# InputChannel_2.net
KiCad netlist of a schematic drawn in Altium Designer
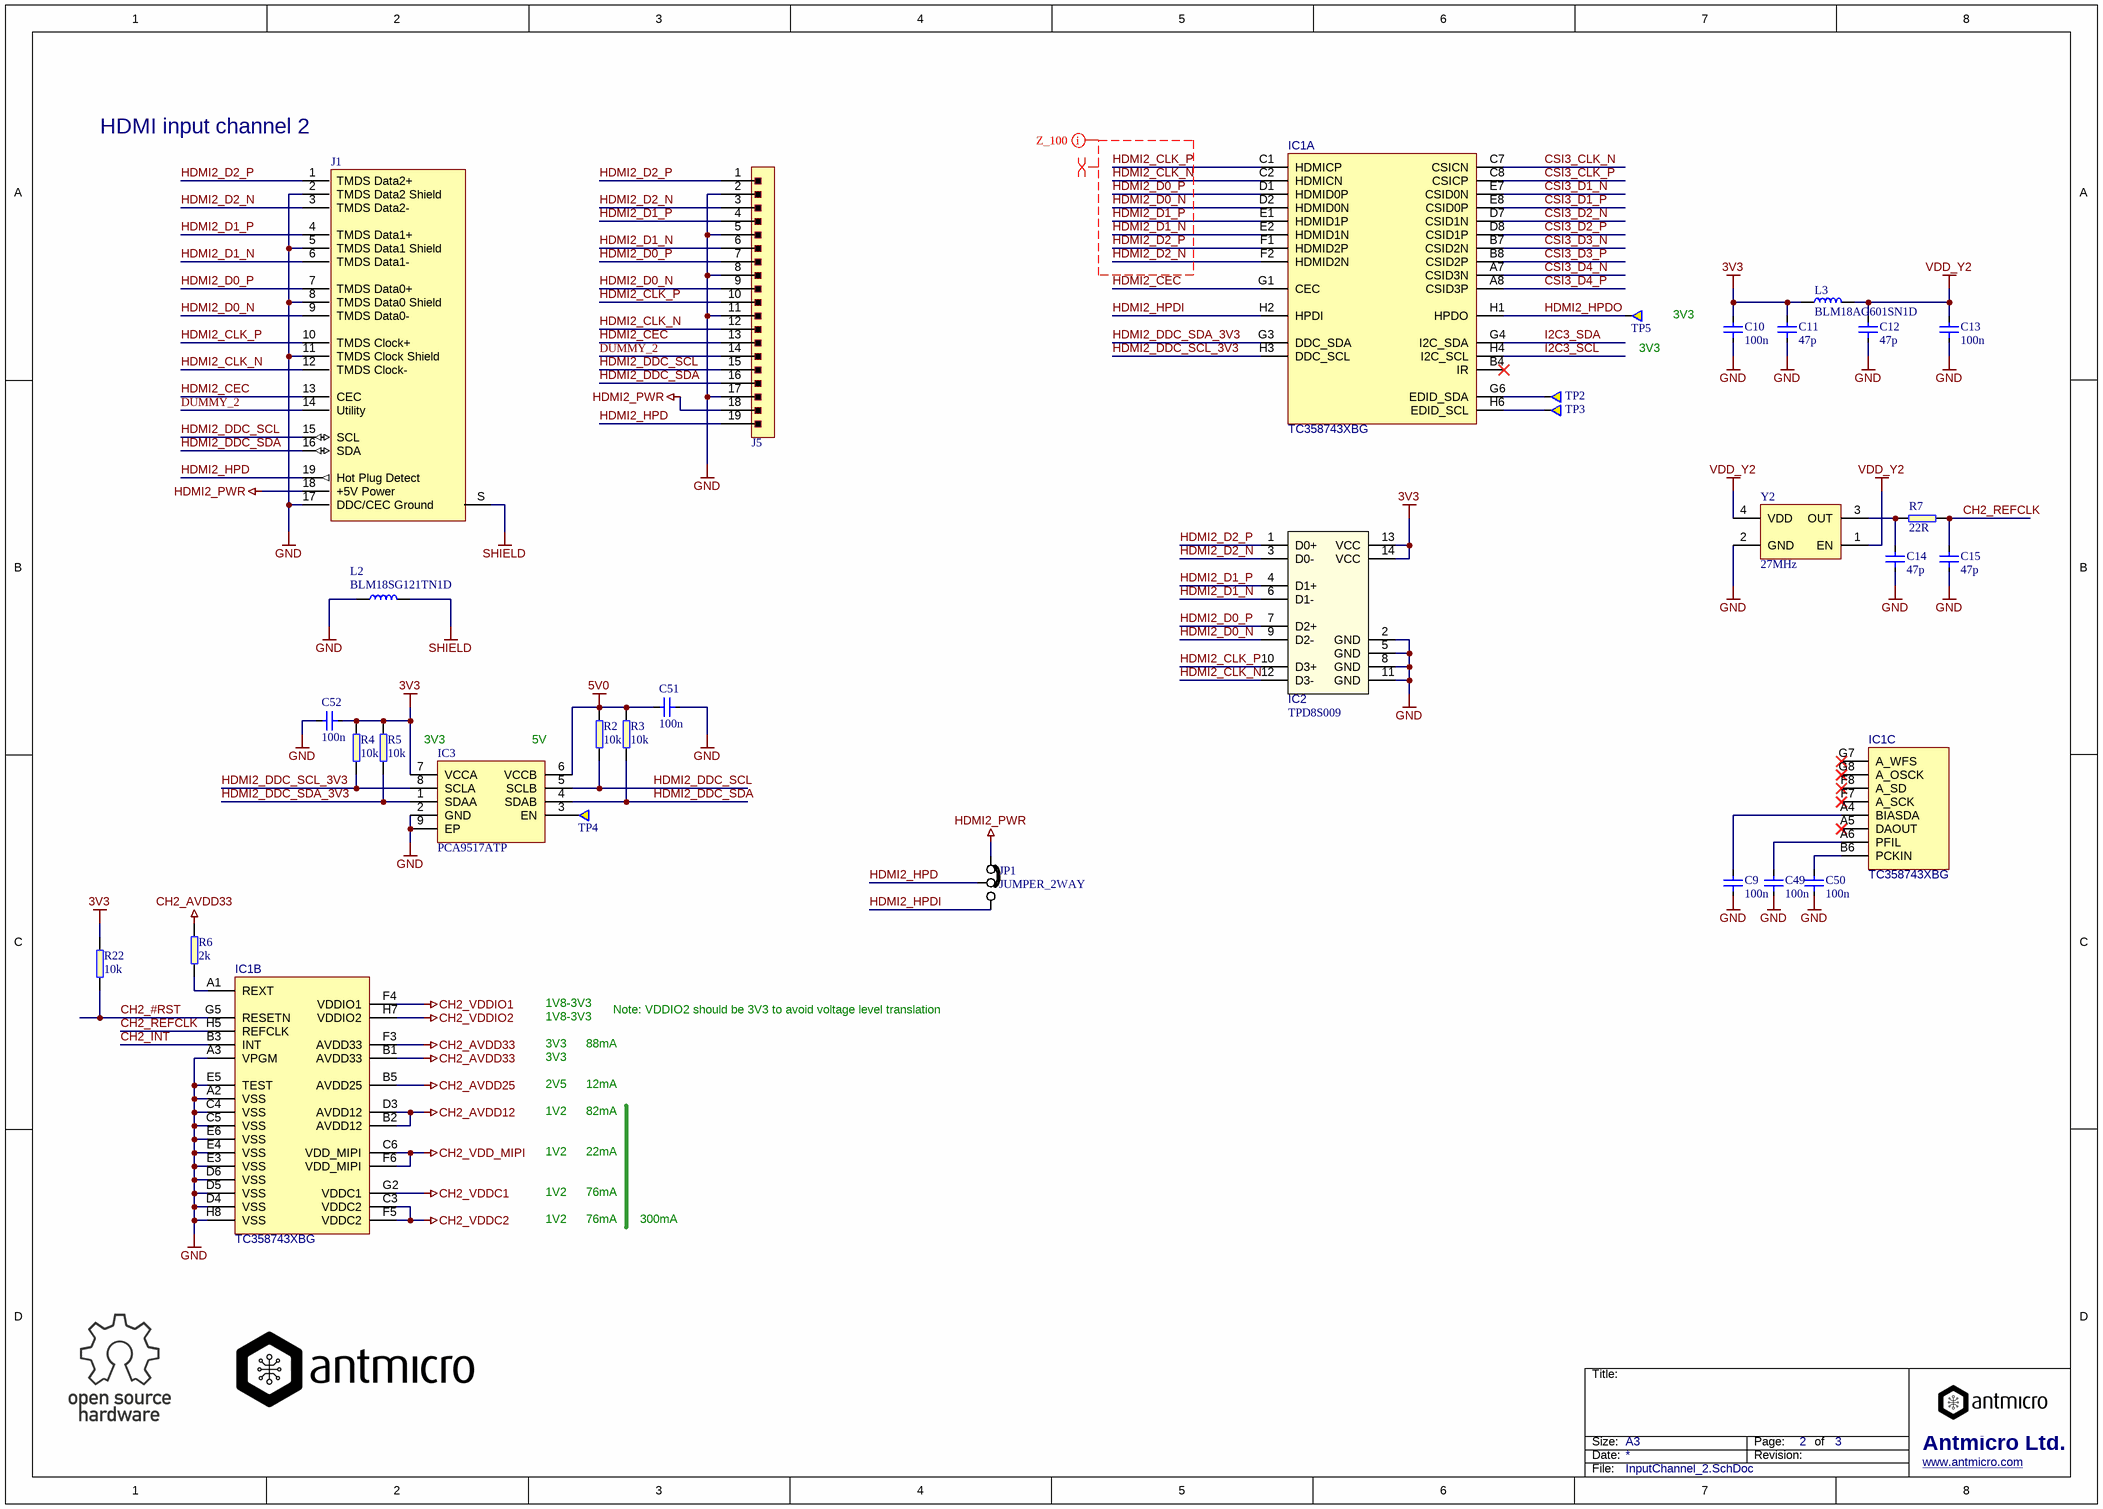
[diagram p0: InputChannel_2.SchDoc]

(export (version "E")
  (design (tool "Eeschema 10.0.6"))
  (components
    (comp (ref "C9")
      (value "100n")
      (footprint "HDMI-MIPI-Bridge:0402")
      (description "MLCC SMT Capacitor 100nF 0402")
      (fields (field (name "PART NUMBER") "C_100n_0402") (field (name "MANUFACTURER") "MULTICOMP"))
      (libsource (lib "AntmicroComponents") (part "C"))
    )
    (comp (ref "C10")
      (value "100n")
      (footprint "HDMI-MIPI-Bridge:0402")
      (description "MLCC SMT Capacitor 100nF 0402")
      (fields (field (name "PART NUMBER") "C_100n_0402") (field (name "MANUFACTURER") "MULTICOMP"))
      (libsource (lib "AntmicroComponents") (part "C"))
    )
    (comp (ref "C11")
      (value "47p")
      (footprint "HDMI-MIPI-Bridge:0402")
      (description "MLCC SMT Capacitor 47pF 0402")
      (fields (field (name "PART NUMBER") "C_47p_0402") (field (name "MANUFACTURER") "KEMET"))
      (libsource (lib "AntmicroComponents") (part "C"))
    )
    (comp (ref "C12")
      (value "47p")
      (footprint "HDMI-MIPI-Bridge:0402")
      (description "MLCC SMT Capacitor 47pF 0402")
      (fields (field (name "PART NUMBER") "C_47p_0402") (field (name "MANUFACTURER") "KEMET"))
      (libsource (lib "AntmicroComponents") (part "C"))
    )
    (comp (ref "C13")
      (value "100n")
      (footprint "HDMI-MIPI-Bridge:0402")
      (description "MLCC SMT Capacitor 100nF 0402")
      (fields (field (name "PART NUMBER") "C_100n_0402") (field (name "MANUFACTURER") "MULTICOMP"))
      (libsource (lib "AntmicroComponents") (part "C"))
    )
    (comp (ref "C14")
      (value "47p")
      (footprint "HDMI-MIPI-Bridge:0402")
      (description "MLCC SMT Capacitor 47pF 0402")
      (fields (field (name "PART NUMBER") "C_47p_0402") (field (name "MANUFACTURER") "KEMET"))
      (libsource (lib "AntmicroComponents") (part "C"))
    )
    (comp (ref "C15")
      (value "47p")
      (footprint "HDMI-MIPI-Bridge:0402")
      (description "MLCC SMT Capacitor 47pF 0402")
      (fields (field (name "PART NUMBER") "C_47p_0402") (field (name "MANUFACTURER") "KEMET"))
      (libsource (lib "AntmicroComponents") (part "C"))
    )
    (comp (ref "C49")
      (value "100n")
      (footprint "HDMI-MIPI-Bridge:0402")
      (description "MLCC SMT Capacitor 100nF 0402")
      (fields (field (name "PART NUMBER") "C_100n_0402") (field (name "MANUFACTURER") "MULTICOMP"))
      (libsource (lib "AntmicroComponents") (part "C"))
    )
    (comp (ref "C50")
      (value "100n")
      (footprint "HDMI-MIPI-Bridge:0402")
      (description "MLCC SMT Capacitor 100nF 0402")
      (fields (field (name "PART NUMBER") "C_100n_0402") (field (name "MANUFACTURER") "MULTICOMP"))
      (libsource (lib "AntmicroComponents") (part "C"))
    )
    (comp (ref "C51")
      (value "100n")
      (footprint "HDMI-MIPI-Bridge:0402")
      (description "MLCC SMT Capacitor 100nF 0402")
      (fields (field (name "PART NUMBER") "C_100n_0402") (field (name "MANUFACTURER") "MULTICOMP"))
      (libsource (lib "AntmicroComponents") (part "C"))
    )
    (comp (ref "C52")
      (value "100n")
      (footprint "HDMI-MIPI-Bridge:0402")
      (description "MLCC SMT Capacitor 100nF 0402")
      (fields (field (name "PART NUMBER") "C_100n_0402") (field (name "MANUFACTURER") "MULTICOMP"))
      (libsource (lib "AntmicroComponents") (part "C"))
    )
    (comp (ref "IC1")
      (value "TC358743XBG")
      (footprint "HDMI-MIPI-Bridge:TC358743XBG")
      (description "Toshiba TC358743XBG HDMI-CSI bridge")
      (fields (field (name "MANUFACTURER") "Toshiba"))
      (libsource (lib "AntmicroComponents") (part "TC358743XBG"))
    )
    (comp (ref "IC2")
      (value "TPD8S009")
      (footprint "HDMI-MIPI-Bridge:SON-15")
      (description "8-Channel ESD Protection for DisplayPort and HDMI")
      (fields (field (name "MANUFACTURER") "TEXAS INSTRUMENTS") (field (name "MPN") "TPD8S009DSMR"))
      (libsource (lib "AntmicroComponents") (part "TPD8S009"))
    )
    (comp (ref "IC3")
      (value "PCA9517ATP")
      (footprint "HDMI-MIPI-Bridge:PCA9517ATP")
      (description "I2C BUS REPEATER W/ LEVEL TRANS, HWSON-8")
      (fields (field (name "MANUFACTURER") "NXP"))
      (libsource (lib "AntmicroComponents") (part "PCA9517ATP"))
    )
    (comp (ref "J1")
      (value "~")
      (footprint "HDMI-MIPI-Bridge:Molex_HDMI_471511001")
      (description "Header right angle HDMI")
      (fields (field (name "PART NUMBER") "CON-Molex-471511001") (field (name "MANUFACTURER") "MOLEX"))
      (libsource (lib "AntmicroComponents") (part "CON-Molex-471511001"))
    )
    (comp (ref "J5")
      (value "Molex-505110-1992")
      (footprint "HDMI-MIPI-Bridge:CON-Molex-505110-1992")
      (description "FPC socket 19 pins")
      (fields (field (name "PART NUMBER") "CON-Molex-505110-1992") (field (name "MANUFACTURER") "Molex"))
      (libsource (lib "AntmicroComponents") (part "1X19"))
    )
    (comp (ref "JP1")
      (value "JUMPER_2WAY")
      (footprint "HDMI-MIPI-Bridge:JUMPER_2WAY")
      (description "Solder jumper")
      (fields (field (name "PART NUMBER") "Jumper 2 way"))
      (libsource (lib "AntmicroComponents") (part "JUMPER_2WAY"))
    )
    (comp (ref "L2")
      (value "BLM18SG121TN1D")
      (footprint "HDMI-MIPI-Bridge:0603")
      (description "FERRITE BEAD, 0.025OHM, 3A, 0603")
      (fields (field (name "MANUFACTURER") "MURATA"))
      (libsource (lib "AntmicroComponents") (part "Inductor SMT"))
    )
    (comp (ref "L3")
      (value "BLM18AG601SN1D")
      (footprint "HDMI-MIPI-Bridge:0603")
      (description "Ferrite Bead, 600 ohm, 0603 [1608 Metric], BLM18A Series, 500 mA, 0.38 ohm, ± 25%")
      (fields (field (name "MANUFACTURER") "MURATA"))
      (libsource (lib "AntmicroComponents") (part "Inductor SMT"))
    )
    (comp (ref "R2")
      (value "10k")
      (footprint "HDMI-MIPI-Bridge:0402")
      (description "SMT Resistor 0402")
      (fields (field (name "PART NUMBER") "R_10k_0402") (field (name "MANUFACTURER") "MULTICOMP"))
      (libsource (lib "AntmicroComponents") (part "R"))
    )
    (comp (ref "R3")
      (value "10k")
      (footprint "HDMI-MIPI-Bridge:0402")
      (description "SMT Resistor 0402")
      (fields (field (name "PART NUMBER") "R_10k_0402") (field (name "MANUFACTURER") "MULTICOMP"))
      (libsource (lib "AntmicroComponents") (part "R"))
    )
    (comp (ref "R4")
      (value "10k")
      (footprint "HDMI-MIPI-Bridge:0402")
      (description "SMT Resistor 0402")
      (fields (field (name "PART NUMBER") "R_10k_0402") (field (name "MANUFACTURER") "MULTICOMP"))
      (libsource (lib "AntmicroComponents") (part "R"))
    )
    (comp (ref "R5")
      (value "10k")
      (footprint "HDMI-MIPI-Bridge:0402")
      (description "SMT Resistor 0402")
      (fields (field (name "PART NUMBER") "R_10k_0402") (field (name "MANUFACTURER") "MULTICOMP"))
      (libsource (lib "AntmicroComponents") (part "R"))
    )
    (comp (ref "R6")
      (value "2k")
      (footprint "HDMI-MIPI-Bridge:0603")
      (description "SMT Resistor 2k 0603")
      (fields (field (name "PART NUMBER") "R_2k_0603") (field (name "MANUFACTURER") "MULTICOMP"))
      (libsource (lib "AntmicroComponents") (part "R"))
    )
    (comp (ref "R7")
      (value "22R")
      (footprint "HDMI-MIPI-Bridge:0402")
      (description "SMT Resistor 22R 0402")
      (fields (field (name "PART NUMBER") "R_22R_0402") (field (name "MANUFACTURER") "VISHAY"))
      (libsource (lib "") (part "R_1"))
    )
    (comp (ref "R22")
      (value "10k")
      (footprint "HDMI-MIPI-Bridge:0402")
      (description "SMT Resistor 0402")
      (fields (field (name "PART NUMBER") "R_10k_0402") (field (name "MANUFACTURER") "MULTICOMP"))
      (libsource (lib "AntmicroComponents") (part "R"))
    )
    (comp (ref "TP2")
      (value "Testpad")
      (footprint "HDMI-MIPI-Bridge:TP-R-1")
      (description "Testpad, round, 1mm")
      (fields (field (name "PART NUMBER") "TP-R-1"))
      (libsource (lib "AntmicroComponents") (part "Testpad"))
    )
    (comp (ref "TP3")
      (value "Testpad")
      (footprint "HDMI-MIPI-Bridge:TP-R-1")
      (description "Testpad, round, 1mm")
      (fields (field (name "PART NUMBER") "TP-R-1"))
      (libsource (lib "AntmicroComponents") (part "Testpad"))
    )
    (comp (ref "TP4")
      (value "Testpad")
      (footprint "HDMI-MIPI-Bridge:TP-R-1")
      (description "Testpad, round, 1mm")
      (fields (field (name "PART NUMBER") "TP-R-1"))
      (libsource (lib "AntmicroComponents") (part "Testpad"))
    )
    (comp (ref "TP5")
      (value "Testpad")
      (footprint "HDMI-MIPI-Bridge:TP-R-1")
      (description "Testpad, round, 1mm")
      (fields (field (name "PART NUMBER") "TP-R-1"))
      (libsource (lib "AntmicroComponents") (part "Testpad"))
    )
    (comp (ref "Y2")
      (value "27MHz")
      (footprint "HDMI-MIPI-Bridge:TXC_7C")
      (description "OSC, 27.000MHZ, 3.3V, SMD, 5.0X3.2")
      (fields (field (name "PART NUMBER") "7C-27.000MBB-T") (field (name "MANUFACTURER") "TXC"))
      (libsource (lib "AntmicroComponents") (part "TXC_7C"))
    )
  )
  (nets
    (net (code "1") (name "/CH2_#RST") (class "Default")
      (node (ref "IC1") (pin "G5") (pinfunction "RESETN_G5") (pintype "passive"))
      (node (ref "R22") (pin "1") (pintype "passive"))
    )
    (net (code "2") (name "/CH2_INT") (class "Default")
      (node (ref "IC1") (pin "B3") (pinfunction "INT_B3") (pintype "passive"))
    )
    (net (code "3") (name "/CH2_REFCLK") (class "Default")
      (node (ref "C15") (pin "2") (pinfunction "2_2") (pintype "passive"))
      (node (ref "IC1") (pin "H5") (pinfunction "REFCLK_H5") (pintype "passive"))
      (node (ref "R7") (pin "2") (pintype "passive"))
    )
    (net (code "4") (name "/CSI3_CLK_N") (class "Default")
      (node (ref "IC1") (pin "C7") (pinfunction "CSICN_C7") (pintype "passive"))
    )
    (net (code "5") (name "/CSI3_CLK_P") (class "Default")
      (node (ref "IC1") (pin "C8") (pinfunction "CSICP_C8") (pintype "passive"))
    )
    (net (code "6") (name "/CSI3_D1_N") (class "Default")
      (node (ref "IC1") (pin "E7") (pinfunction "CSID0N_E7") (pintype "passive"))
    )
    (net (code "7") (name "/CSI3_D1_P") (class "Default")
      (node (ref "IC1") (pin "E8") (pinfunction "CSID0P_E8") (pintype "passive"))
    )
    (net (code "8") (name "/CSI3_D2_N") (class "Default")
      (node (ref "IC1") (pin "D7") (pinfunction "CSID1N_D7") (pintype "passive"))
    )
    (net (code "9") (name "/CSI3_D2_P") (class "Default")
      (node (ref "IC1") (pin "D8") (pinfunction "CSID1P_D8") (pintype "passive"))
    )
    (net (code "10") (name "/CSI3_D3_N") (class "Default")
      (node (ref "IC1") (pin "B7") (pinfunction "CSID2N_B7") (pintype "passive"))
    )
    (net (code "11") (name "/CSI3_D3_P") (class "Default")
      (node (ref "IC1") (pin "B8") (pinfunction "CSID2P_B8") (pintype "passive"))
    )
    (net (code "12") (name "/CSI3_D4_N") (class "Default")
      (node (ref "IC1") (pin "A7") (pinfunction "CSID3N_A7") (pintype "passive"))
    )
    (net (code "13") (name "/CSI3_D4_P") (class "Default")
      (node (ref "IC1") (pin "A8") (pinfunction "CSID3P_A8") (pintype "passive"))
    )
    (net (code "14") (name "/DUMMY_2") (class "Default")
      (node (ref "J1") (pin "14") (pinfunction "Utility_14") (pintype "passive"))
      (node (ref "J5") (pin "14") (pinfunction "14_14") (pintype "passive"))
    )
    (net (code "15") (name "/HDMI2_CEC") (class "Default")
      (node (ref "IC1") (pin "G1") (pinfunction "CEC_G1") (pintype "passive"))
      (node (ref "J1") (pin "13") (pinfunction "CEC_13") (pintype "passive"))
      (node (ref "J5") (pin "13") (pinfunction "13_13") (pintype "passive"))
    )
    (net (code "16") (name "/HDMI2_CLK_N") (class "Default")
      (node (ref "IC1") (pin "C2") (pinfunction "HDMICN_C2") (pintype "passive"))
      (node (ref "IC2") (pin "12") (pinfunction "D3-_12") (pintype "passive"))
      (node (ref "J1") (pin "12") (pinfunction "TMDS_Clock-_12") (pintype "passive"))
      (node (ref "J5") (pin "12") (pinfunction "12_12") (pintype "passive"))
    )
    (net (code "17") (name "/HDMI2_CLK_P") (class "Default")
      (node (ref "IC1") (pin "C1") (pinfunction "HDMICP_C1") (pintype "passive"))
      (node (ref "IC2") (pin "10") (pinfunction "D3+_10") (pintype "passive"))
      (node (ref "J1") (pin "10") (pinfunction "TMDS_Clock+_10") (pintype "passive"))
      (node (ref "J5") (pin "10") (pinfunction "10_10") (pintype "passive"))
    )
    (net (code "18") (name "/HDMI2_D0_N") (class "Default")
      (node (ref "IC1") (pin "D2") (pinfunction "HDMID0N_D2") (pintype "passive"))
      (node (ref "IC2") (pin "9") (pinfunction "D2-_9") (pintype "passive"))
      (node (ref "J1") (pin "9") (pinfunction "TMDS_Data0-_9") (pintype "passive"))
      (node (ref "J5") (pin "9") (pinfunction "9_9") (pintype "passive"))
    )
    (net (code "19") (name "/HDMI2_D0_P") (class "Default")
      (node (ref "IC1") (pin "D1") (pinfunction "HDMID0P_D1") (pintype "passive"))
      (node (ref "IC2") (pin "7") (pinfunction "D2+_7") (pintype "passive"))
      (node (ref "J1") (pin "7") (pinfunction "TMDS_Data0+_7") (pintype "passive"))
      (node (ref "J5") (pin "7") (pinfunction "7_7") (pintype "passive"))
    )
    (net (code "20") (name "/HDMI2_D1_N") (class "Default")
      (node (ref "IC1") (pin "E2") (pinfunction "HDMID1N_E2") (pintype "passive"))
      (node (ref "IC2") (pin "6") (pinfunction "D1-_6") (pintype "passive"))
      (node (ref "J1") (pin "6") (pinfunction "TMDS_Data1-_6") (pintype "passive"))
      (node (ref "J5") (pin "6") (pinfunction "6_6") (pintype "passive"))
    )
    (net (code "21") (name "/HDMI2_D1_P") (class "Default")
      (node (ref "IC1") (pin "E1") (pinfunction "HDMID1P_E1") (pintype "passive"))
      (node (ref "IC2") (pin "4") (pinfunction "D1+_4") (pintype "passive"))
      (node (ref "J1") (pin "4") (pinfunction "TMDS_Data1+_4") (pintype "passive"))
      (node (ref "J5") (pin "4") (pinfunction "4_4") (pintype "passive"))
    )
    (net (code "22") (name "/HDMI2_D2_N") (class "Default")
      (node (ref "IC1") (pin "F2") (pinfunction "HDMID2N_F2") (pintype "passive"))
      (node (ref "IC2") (pin "3") (pinfunction "D0-_3") (pintype "passive"))
      (node (ref "J1") (pin "3") (pinfunction "TMDS_Data2-_3") (pintype "passive"))
      (node (ref "J5") (pin "3") (pinfunction "3_3") (pintype "passive"))
    )
    (net (code "23") (name "/HDMI2_D2_P") (class "Default")
      (node (ref "IC1") (pin "F1") (pinfunction "HDMID2P_F1") (pintype "passive"))
      (node (ref "IC2") (pin "1") (pinfunction "D0+_1") (pintype "passive"))
      (node (ref "J1") (pin "1") (pinfunction "TMDS_Data2+_1") (pintype "passive"))
      (node (ref "J5") (pin "1") (pinfunction "1_1") (pintype "passive"))
    )
    (net (code "24") (name "/HDMI2_DDC_SCL") (class "Default")
      (node (ref "IC3") (pin "5") (pinfunction "SCLB_5") (pintype "passive"))
      (node (ref "J1") (pin "15") (pinfunction "SCL_15") (pintype "bidirectional"))
      (node (ref "J5") (pin "15") (pinfunction "15_15") (pintype "passive"))
      (node (ref "R2") (pin "1") (pintype "passive"))
    )
    (net (code "25") (name "/HDMI2_DDC_SCL_3V3") (class "Default")
      (node (ref "IC1") (pin "H3") (pinfunction "DDC_SCL_H3") (pintype "passive"))
      (node (ref "IC3") (pin "8") (pinfunction "SCLA_8") (pintype "passive"))
      (node (ref "R4") (pin "1") (pintype "passive"))
    )
    (net (code "26") (name "/HDMI2_DDC_SDA") (class "Default")
      (node (ref "IC3") (pin "4") (pinfunction "SDAB_4") (pintype "passive"))
      (node (ref "J1") (pin "16") (pinfunction "SDA_16") (pintype "bidirectional"))
      (node (ref "J5") (pin "16") (pinfunction "16_16") (pintype "passive"))
      (node (ref "R3") (pin "1") (pintype "passive"))
    )
    (net (code "27") (name "/HDMI2_DDC_SDA_3V3") (class "Default")
      (node (ref "IC1") (pin "G3") (pinfunction "DDC_SDA_G3") (pintype "passive"))
      (node (ref "IC3") (pin "1") (pinfunction "SDAA_1") (pintype "passive"))
      (node (ref "R5") (pin "1") (pintype "passive"))
    )
    (net (code "28") (name "/HDMI2_HPD") (class "Default")
      (node (ref "J1") (pin "19") (pinfunction "Hot_Plug_Detect_19") (pintype "output"))
      (node (ref "J5") (pin "19") (pinfunction "19_19") (pintype "passive"))
      (node (ref "JP1") (pin "2") (pinfunction "2_2") (pintype "passive"))
    )
    (net (code "29") (name "/HDMI2_HPDI") (class "Default")
      (node (ref "IC1") (pin "H2") (pinfunction "HPDI_H2") (pintype "passive"))
      (node (ref "JP1") (pin "3") (pinfunction "3_3") (pintype "passive"))
    )
    (net (code "30") (name "/HDMI2_HPDO") (class "Default")
      (node (ref "IC1") (pin "H1") (pinfunction "HPDO_H1") (pintype "passive"))
      (node (ref "TP5") (pin "1") (pintype "passive"))
    )
    (net (code "31") (name "/I2C3_SCL") (class "Default")
      (node (ref "IC1") (pin "H4") (pinfunction "I2C_SCL_H4") (pintype "passive"))
    )
    (net (code "32") (name "/I2C3_SDA") (class "Default")
      (node (ref "IC1") (pin "G4") (pinfunction "I2C_SDA_G4") (pintype "passive"))
    )
    (net (code "33") (name "3V3") (class "Default")
      (node (ref "C10") (pin "2") (pinfunction "2_2") (pintype "passive"))
      (node (ref "C11") (pin "2") (pinfunction "2_2") (pintype "passive"))
      (node (ref "C52") (pin "1") (pinfunction "1_1") (pintype "passive"))
      (node (ref "IC2") (pin "13") (pinfunction "VCC_13") (pintype "passive"))
      (node (ref "IC2") (pin "14") (pinfunction "VCC_14") (pintype "passive"))
      (node (ref "IC3") (pin "7") (pinfunction "VCCA_7") (pintype "passive"))
      (node (ref "L3") (pin "1") (pintype "passive"))
      (node (ref "R22") (pin "2") (pintype "passive"))
      (node (ref "R4") (pin "2") (pintype "passive"))
      (node (ref "R5") (pin "2") (pintype "passive"))
    )
    (net (code "34") (name "5V0") (class "Default")
      (node (ref "C51") (pin "2") (pinfunction "2_2") (pintype "passive"))
      (node (ref "IC3") (pin "6") (pinfunction "VCCB_6") (pintype "passive"))
      (node (ref "R2") (pin "2") (pintype "passive"))
      (node (ref "R3") (pin "2") (pintype "passive"))
    )
    (net (code "35") (name "CH2_AVDD12") (class "Default")
      (node (ref "IC1") (pin "B2") (pinfunction "AVDD12_B2") (pintype "passive"))
      (node (ref "IC1") (pin "D3") (pinfunction "AVDD12_D3") (pintype "passive"))
    )
    (net (code "36") (name "CH2_AVDD25") (class "Default")
      (node (ref "IC1") (pin "B5") (pinfunction "AVDD25_B5") (pintype "passive"))
    )
    (net (code "37") (name "CH2_AVDD33") (class "Default")
      (node (ref "IC1") (pin "B1") (pinfunction "AVDD33_B1") (pintype "passive"))
      (node (ref "IC1") (pin "F3") (pinfunction "AVDD33_F3") (pintype "passive"))
      (node (ref "R6") (pin "2") (pintype "passive"))
    )
    (net (code "38") (name "CH2_VDDC1") (class "Default")
      (node (ref "IC1") (pin "G2") (pinfunction "VDDC1_G2") (pintype "passive"))
    )
    (net (code "39") (name "CH2_VDDC2") (class "Default")
      (node (ref "IC1") (pin "C3") (pinfunction "VDDC2_C3") (pintype "passive"))
      (node (ref "IC1") (pin "F5") (pinfunction "VDDC2_F5") (pintype "passive"))
    )
    (net (code "40") (name "CH2_VDDIO1") (class "Default")
      (node (ref "IC1") (pin "F4") (pinfunction "VDDIO1_F4") (pintype "passive"))
    )
    (net (code "41") (name "CH2_VDDIO2") (class "Default")
      (node (ref "IC1") (pin "H7") (pinfunction "VDDIO2_H7") (pintype "passive"))
    )
    (net (code "42") (name "CH2_VDD_MIPI") (class "Default")
      (node (ref "IC1") (pin "C6") (pinfunction "VDD_MIPI_C6") (pintype "passive"))
      (node (ref "IC1") (pin "F6") (pinfunction "VDD_MIPI_F6") (pintype "passive"))
    )
    (net (code "43") (name "GND") (class "Default")
      (node (ref "C10") (pin "1") (pinfunction "1_1") (pintype "passive"))
      (node (ref "C11") (pin "1") (pinfunction "1_1") (pintype "passive"))
      (node (ref "C12") (pin "1") (pinfunction "1_1") (pintype "passive"))
      (node (ref "C13") (pin "1") (pinfunction "1_1") (pintype "passive"))
      (node (ref "C14") (pin "1") (pinfunction "1_1") (pintype "passive"))
      (node (ref "C15") (pin "1") (pinfunction "1_1") (pintype "passive"))
      (node (ref "C49") (pin "1") (pinfunction "1_1") (pintype "passive"))
      (node (ref "C50") (pin "1") (pinfunction "1_1") (pintype "passive"))
      (node (ref "C51") (pin "1") (pinfunction "1_1") (pintype "passive"))
      (node (ref "C52") (pin "2") (pinfunction "2_2") (pintype "passive"))
      (node (ref "C9") (pin "1") (pinfunction "1_1") (pintype "passive"))
      (node (ref "IC1") (pin "A2") (pinfunction "VSS_A2") (pintype "passive"))
      (node (ref "IC1") (pin "A3") (pinfunction "VPGM_A3") (pintype "passive"))
      (node (ref "IC1") (pin "C4") (pinfunction "VSS_C4") (pintype "passive"))
      (node (ref "IC1") (pin "C5") (pinfunction "VSS_C5") (pintype "passive"))
      (node (ref "IC1") (pin "D4") (pinfunction "VSS_D4") (pintype "passive"))
      (node (ref "IC1") (pin "D5") (pinfunction "VSS_D5") (pintype "passive"))
      (node (ref "IC1") (pin "D6") (pinfunction "VSS_D6") (pintype "passive"))
      (node (ref "IC1") (pin "E3") (pinfunction "VSS_E3") (pintype "passive"))
      (node (ref "IC1") (pin "E4") (pinfunction "VSS_E4") (pintype "passive"))
      (node (ref "IC1") (pin "E5") (pinfunction "TEST_E5") (pintype "passive"))
      (node (ref "IC1") (pin "E6") (pinfunction "VSS_E6") (pintype "passive"))
      (node (ref "IC1") (pin "H8") (pinfunction "VSS_H8") (pintype "passive"))
      (node (ref "IC2") (pin "11") (pinfunction "GND_11") (pintype "passive"))
      (node (ref "IC2") (pin "2") (pinfunction "GND_2") (pintype "passive"))
      (node (ref "IC2") (pin "5") (pinfunction "GND_5") (pintype "passive"))
      (node (ref "IC2") (pin "8") (pinfunction "GND_8") (pintype "passive"))
      (node (ref "IC3") (pin "2") (pinfunction "GND_2") (pintype "passive"))
      (node (ref "IC3") (pin "9") (pinfunction "EP_9") (pintype "passive"))
      (node (ref "J1") (pin "11") (pinfunction "TMDS_Clock_Shield_11") (pintype "passive"))
      (node (ref "J1") (pin "17") (pinfunction "DDC/CEC_Ground_17") (pintype "power_in"))
      (node (ref "J1") (pin "2") (pinfunction "TMDS_Data2_Shield_2") (pintype "passive"))
      (node (ref "J1") (pin "5") (pinfunction "TMDS_Data1_Shield_5") (pintype "passive"))
      (node (ref "J1") (pin "8") (pinfunction "TMDS_Data0_Shield_8") (pintype "passive"))
      (node (ref "J5") (pin "11") (pinfunction "11_11") (pintype "passive"))
      (node (ref "J5") (pin "17") (pinfunction "17_17") (pintype "passive"))
      (node (ref "J5") (pin "2") (pinfunction "2_2") (pintype "passive"))
      (node (ref "J5") (pin "5") (pinfunction "5_5") (pintype "passive"))
      (node (ref "J5") (pin "8") (pinfunction "8_8") (pintype "passive"))
      (node (ref "L2") (pin "1") (pintype "passive"))
      (node (ref "Y2") (pin "2") (pinfunction "GND_2") (pintype "passive"))
    )
    (net (code "44") (name "HDMI2_PWR") (class "Default")
      (node (ref "J1") (pin "18") (pinfunction "+5V_Power_18") (pintype "power_in"))
      (node (ref "J5") (pin "18") (pinfunction "18_18") (pintype "passive"))
      (node (ref "JP1") (pin "1") (pinfunction "1_1") (pintype "passive"))
    )
    (net (code "45") (name "Net-(IC1A-EDID_SCL)") (class "Default")
      (node (ref "IC1") (pin "H6") (pinfunction "EDID_SCL_H6") (pintype "passive"))
      (node (ref "TP3") (pin "1") (pintype "passive"))
    )
    (net (code "46") (name "Net-(IC1A-EDID_SDA)") (class "Default")
      (node (ref "IC1") (pin "G6") (pinfunction "EDID_SDA_G6") (pintype "passive"))
      (node (ref "TP2") (pin "1") (pintype "passive"))
    )
    (net (code "47") (name "Net-(IC1B-REXT)") (class "Default")
      (node (ref "IC1") (pin "A1") (pinfunction "REXT_A1") (pintype "passive"))
      (node (ref "R6") (pin "1") (pintype "passive"))
    )
    (net (code "48") (name "Net-(IC1C-BIASDA)") (class "Default")
      (node (ref "C9") (pin "2") (pinfunction "2_2") (pintype "passive"))
      (node (ref "IC1") (pin "A4") (pinfunction "BIASDA_A4") (pintype "passive"))
    )
    (net (code "49") (name "Net-(IC1C-PCKIN)") (class "Default")
      (node (ref "C50") (pin "2") (pinfunction "2_2") (pintype "passive"))
      (node (ref "IC1") (pin "B6") (pinfunction "PCKIN_B6") (pintype "passive"))
    )
    (net (code "50") (name "Net-(IC1C-PFIL)") (class "Default")
      (node (ref "C49") (pin "2") (pinfunction "2_2") (pintype "passive"))
      (node (ref "IC1") (pin "A6") (pinfunction "PFIL_A6") (pintype "passive"))
    )
    (net (code "51") (name "Net-(IC3-EN)") (class "Default")
      (node (ref "IC3") (pin "3") (pinfunction "EN_3") (pintype "passive"))
      (node (ref "TP4") (pin "1") (pintype "passive"))
    )
    (net (code "52") (name "Net-(Y2-OUT)") (class "Default")
      (node (ref "C14") (pin "2") (pinfunction "2_2") (pintype "passive"))
      (node (ref "R7") (pin "1") (pintype "passive"))
      (node (ref "Y2") (pin "3") (pinfunction "OUT_3") (pintype "passive"))
    )
    (net (code "53") (name "SHIELD") (class "Default")
      (node (ref "J1") (pin "S") (pinfunction "SH_S") (pintype "passive"))
      (node (ref "L2") (pin "2") (pintype "passive"))
    )
    (net (code "54") (name "VDD_Y2") (class "Default")
      (node (ref "C12") (pin "2") (pinfunction "2_2") (pintype "passive"))
      (node (ref "C13") (pin "2") (pinfunction "2_2") (pintype "passive"))
      (node (ref "L3") (pin "2") (pintype "passive"))
      (node (ref "Y2") (pin "1") (pinfunction "EN_1") (pintype "passive"))
      (node (ref "Y2") (pin "4") (pinfunction "VDD_4") (pintype "passive"))
    )
    (net (code "55") (name "unconnected-(IC1A-IR-PadB4)") (class "Default")
      (node (ref "IC1") (pin "B4") (pinfunction "IR_B4") (pintype "passive+no_connect"))
    )
    (net (code "56") (name "unconnected-(IC1C-A_OSCK-PadG8)") (class "Default")
      (node (ref "IC1") (pin "G8") (pinfunction "A_OSCK_G8") (pintype "passive+no_connect"))
    )
    (net (code "57") (name "unconnected-(IC1C-A_SCK-PadF7)") (class "Default")
      (node (ref "IC1") (pin "F7") (pinfunction "A_SCK_F7") (pintype "passive+no_connect"))
    )
    (net (code "58") (name "unconnected-(IC1C-A_SD-PadF8)") (class "Default")
      (node (ref "IC1") (pin "F8") (pinfunction "A_SD_F8") (pintype "passive+no_connect"))
    )
    (net (code "59") (name "unconnected-(IC1C-A_WFS-PadG7)") (class "Default")
      (node (ref "IC1") (pin "G7") (pinfunction "A_WFS_G7") (pintype "passive+no_connect"))
    )
    (net (code "60") (name "unconnected-(IC1C-DAOUT-PadA5)") (class "Default")
      (node (ref "IC1") (pin "A5") (pinfunction "DAOUT_A5") (pintype "passive+no_connect"))
    )
  )
)
